# tiny85_activity_led.net
KiCad netlist of a schematic drawn in EAGLE
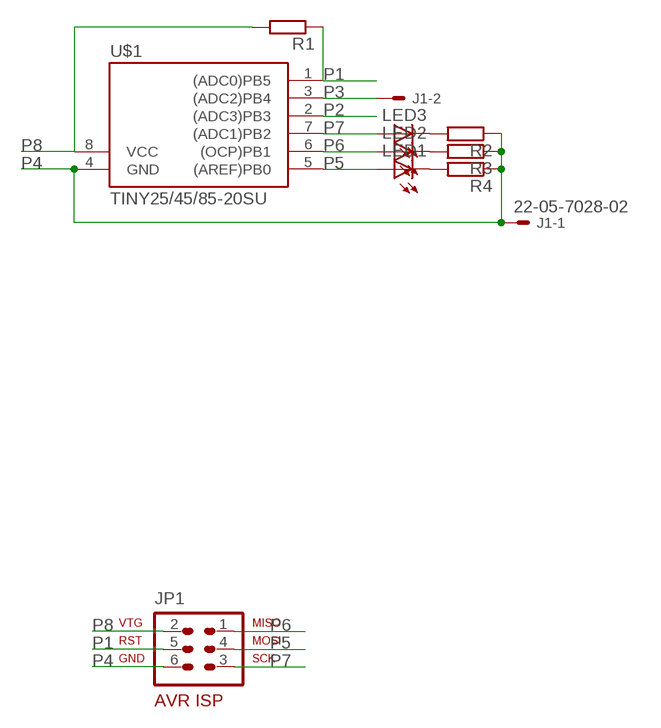
[diagram p0: schematic, sheet 1]

(export (version "E")
  (design (tool "Eeschema 10.0.6"))
  (components
    (comp (ref "J1")
      (value "22-05-7028-02")
      (footprint "eagle-import:7395-02")
      (fields (field (name "MF") "MOLEX"))
      (libsource (lib "eagle-import") (part "22-?-0205-7028"))
    )
    (comp (ref "JP1")
      (value "AVR-ISP-6R")
      (footprint "eagle-import:AVR-ISP-6R")
      (libsource (lib "eagle-import") (part "AVR-ISP-6R"))
    )
    (comp (ref "LED1")
      (value "LED10MM")
      (footprint "eagle-import:LED10MM")
      (libsource (lib "eagle-import") (part "LED10MM"))
    )
    (comp (ref "LED2")
      (value "LED10MM")
      (footprint "eagle-import:LED10MM")
      (libsource (lib "eagle-import") (part "LED10MM"))
    )
    (comp (ref "LED3")
      (value "LED10MM")
      (footprint "eagle-import:LED10MM")
      (libsource (lib "eagle-import") (part "LED10MM"))
    )
    (comp (ref "R1")
      (value "R-EU_R0805")
      (footprint "eagle-import:R0805")
      (libsource (lib "eagle-import") (part "R-EU_R0805"))
    )
    (comp (ref "R2")
      (value "R-EU_R0805")
      (footprint "eagle-import:R0805")
      (libsource (lib "eagle-import") (part "R-EU_R0805"))
    )
    (comp (ref "R3")
      (value "R-EU_R0805")
      (footprint "eagle-import:R0805")
      (libsource (lib "eagle-import") (part "R-EU_R0805"))
    )
    (comp (ref "R4")
      (value "R-EU_R0805")
      (footprint "eagle-import:R0805")
      (libsource (lib "eagle-import") (part "R-EU_R0805"))
    )
    (comp (ref "U$1")
      (value "TINY25/45/85-20SU")
      (footprint "eagle-import:SOIC8")
      (libsource (lib "eagle-import") (part "TINY25/45/85-20SU"))
    )
  )
  (nets
    (net (code "1") (name "/P1") (class "Default")
      (node (ref "JP1") (pin "5") (pinfunction "5_5") (pintype "passive"))
      (node (ref "R1") (pin "1") (pinfunction "1_1") (pintype "passive"))
      (node (ref "U$1") (pin "1") (pinfunction "(ADC0)PB5_1") (pintype "bidirectional"))
    )
    (net (code "2") (name "/P2") (class "Default")
      (node (ref "U$1") (pin "2") (pinfunction "(ADC3)PB3_2") (pintype "bidirectional"))
    )
    (net (code "3") (name "/P3") (class "Default")
      (node (ref "J1") (pin "2") (pinfunction "S_2") (pintype "passive"))
      (node (ref "U$1") (pin "3") (pinfunction "(ADC2)PB4_3") (pintype "bidirectional"))
    )
    (net (code "4") (name "/P4") (class "Default")
      (node (ref "J1") (pin "1") (pinfunction "S_1") (pintype "passive"))
      (node (ref "JP1") (pin "6") (pinfunction "6_6") (pintype "passive"))
      (node (ref "R2") (pin "1") (pinfunction "1_1") (pintype "passive"))
      (node (ref "R3") (pin "1") (pinfunction "1_1") (pintype "passive"))
      (node (ref "R4") (pin "1") (pinfunction "1_1") (pintype "passive"))
      (node (ref "U$1") (pin "4") (pinfunction "GND_4") (pintype "power_in"))
    )
    (net (code "5") (name "/P5") (class "Default")
      (node (ref "JP1") (pin "4") (pinfunction "4_4") (pintype "passive"))
      (node (ref "LED1") (pin "A") (pinfunction "A_A") (pintype "passive"))
      (node (ref "U$1") (pin "5") (pinfunction "(AREF)PB0_5") (pintype "bidirectional"))
    )
    (net (code "6") (name "/P6") (class "Default")
      (node (ref "JP1") (pin "1") (pinfunction "1_1") (pintype "passive"))
      (node (ref "LED2") (pin "A") (pinfunction "A_A") (pintype "passive"))
      (node (ref "U$1") (pin "6") (pinfunction "(OCP)PB1_6") (pintype "bidirectional"))
    )
    (net (code "7") (name "/P7") (class "Default")
      (node (ref "JP1") (pin "3") (pinfunction "3_3") (pintype "passive"))
      (node (ref "LED3") (pin "A") (pinfunction "A_A") (pintype "passive"))
      (node (ref "U$1") (pin "7") (pinfunction "(ADC1)PB2_7") (pintype "bidirectional"))
    )
    (net (code "8") (name "/P8") (class "Default")
      (node (ref "JP1") (pin "2") (pinfunction "2_2") (pintype "passive"))
      (node (ref "R1") (pin "2") (pinfunction "2_2") (pintype "passive"))
      (node (ref "U$1") (pin "8") (pinfunction "VCC_8") (pintype "power_in"))
    )
    (net (code "9") (name "Net-(LED1-C)") (class "Default")
      (node (ref "LED1") (pin "K") (pinfunction "C_K") (pintype "passive"))
      (node (ref "R4") (pin "2") (pinfunction "2_2") (pintype "passive"))
    )
    (net (code "10") (name "Net-(LED2-C)") (class "Default")
      (node (ref "LED2") (pin "K") (pinfunction "C_K") (pintype "passive"))
      (node (ref "R3") (pin "2") (pinfunction "2_2") (pintype "passive"))
    )
    (net (code "11") (name "Net-(LED3-C)") (class "Default")
      (node (ref "LED3") (pin "K") (pinfunction "C_K") (pintype "passive"))
      (node (ref "R2") (pin "2") (pinfunction "2_2") (pintype "passive"))
    )
  )
)
